# SensorFv.net
KiCad netlist of a schematic drawn in EAGLE
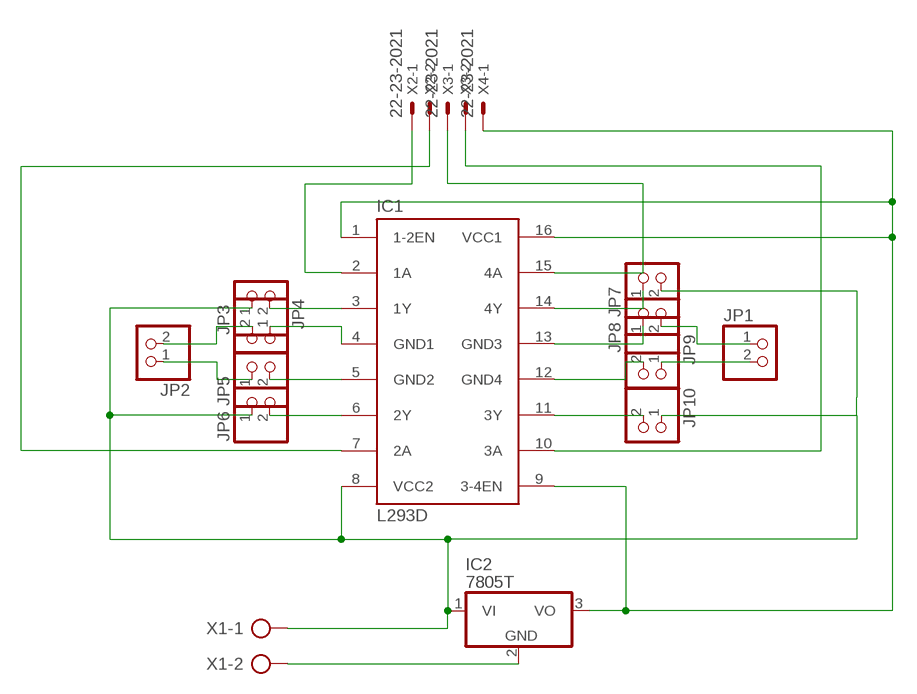
[diagram p0: schematic, sheet 1]

(export (version "E")
  (design (tool "Eeschema 10.0.6"))
  (components
    (comp (ref "IC1")
      (value "L293D")
      (footprint "eagle-import:DIL16")
      (libsource (lib "eagle-import") (part "L293D"))
    )
    (comp (ref "IC2")
      (value "7805T")
      (footprint "eagle-import:TO220H")
      (libsource (lib "eagle-import") (part "78T05"))
    )
    (comp (ref "JP1")
      (value "PINHD-1X2")
      (footprint "eagle-import:1X02")
      (libsource (lib "eagle-import") (part "PINHD-1X2"))
    )
    (comp (ref "JP2")
      (value "PINHD-1X2")
      (footprint "eagle-import:1X02")
      (libsource (lib "eagle-import") (part "PINHD-1X2"))
    )
    (comp (ref "JP3")
      (value "PINHD-1X2")
      (footprint "eagle-import:1X02")
      (libsource (lib "eagle-import") (part "pinhead_325_PINHD-1X2"))
    )
    (comp (ref "JP4")
      (value "PINHD-1X2")
      (footprint "eagle-import:1X02")
      (libsource (lib "eagle-import") (part "pinhead_325_PINHD-1X2"))
    )
    (comp (ref "JP5")
      (value "PINHD-1X2")
      (footprint "eagle-import:1X02")
      (libsource (lib "eagle-import") (part "pinhead_325_PINHD-1X2"))
    )
    (comp (ref "JP6")
      (value "PINHD-1X2")
      (footprint "eagle-import:1X02")
      (libsource (lib "eagle-import") (part "pinhead_325_PINHD-1X2"))
    )
    (comp (ref "JP7")
      (value "PINHD-1X2")
      (footprint "eagle-import:1X02")
      (libsource (lib "eagle-import") (part "pinhead_325_PINHD-1X2"))
    )
    (comp (ref "JP8")
      (value "PINHD-1X2")
      (footprint "eagle-import:1X02")
      (libsource (lib "eagle-import") (part "pinhead_325_PINHD-1X2"))
    )
    (comp (ref "JP9")
      (value "PINHD-1X2")
      (footprint "eagle-import:1X02")
      (libsource (lib "eagle-import") (part "pinhead_325_PINHD-1X2"))
    )
    (comp (ref "JP10")
      (value "PINHD-1X2")
      (footprint "eagle-import:1X02")
      (libsource (lib "eagle-import") (part "pinhead_325_PINHD-1X2"))
    )
    (comp (ref "X1")
      (value "AK500/2-H")
      (footprint "eagle-import:AK500_2-H")
      (libsource (lib "eagle-import") (part "AK500/2-H"))
    )
    (comp (ref "X2")
      (value "22-23-2021")
      (footprint "eagle-import:22-23-2021")
      (fields (field (name "MF") "MOLEX"))
      (libsource (lib "eagle-import") (part "22-23-2021"))
    )
    (comp (ref "X3")
      (value "22-23-2021")
      (footprint "eagle-import:22-23-2021")
      (fields (field (name "MF") "MOLEX"))
      (libsource (lib "eagle-import") (part "22-23-2021"))
    )
    (comp (ref "X4")
      (value "22-23-2021")
      (footprint "eagle-import:22-23-2021")
      (fields (field (name "MF") "MOLEX"))
      (libsource (lib "eagle-import") (part "22-23-2021"))
    )
  )
  (nets
    (net (code "1") (name "Net-(IC1-1-2EN)") (class "Default")
      (node (ref "IC1") (pin "1") (pinfunction "1-2EN_1") (pintype "input"))
      (node (ref "IC1") (pin "16") (pinfunction "VCC1_16") (pintype "power_in"))
      (node (ref "IC1") (pin "9") (pinfunction "3-4EN_9") (pintype "input"))
      (node (ref "IC2") (pin "3") (pinfunction "VO_3") (pintype "passive"))
      (node (ref "X4") (pin "1") (pinfunction "S_1") (pintype "passive"))
    )
    (net (code "2") (name "Net-(IC1-1A)") (class "Default")
      (node (ref "IC1") (pin "2") (pinfunction "1A_2") (pintype "input"))
      (node (ref "X2") (pin "1") (pinfunction "S_1") (pintype "passive"))
    )
    (net (code "3") (name "Net-(IC1-1Y)") (class "Default")
      (node (ref "IC1") (pin "3") (pinfunction "1Y_3") (pintype "output"))
      (node (ref "JP3") (pin "2") (pinfunction "2_2") (pintype "passive"))
    )
    (net (code "4") (name "Net-(IC1-2A)") (class "Default")
      (node (ref "IC1") (pin "7") (pinfunction "2A_7") (pintype "input"))
      (node (ref "X2") (pin "2") (pinfunction "S_2") (pintype "passive"))
    )
    (net (code "5") (name "Net-(IC1-2Y)") (class "Default")
      (node (ref "IC1") (pin "6") (pinfunction "2Y_6") (pintype "output"))
      (node (ref "JP6") (pin "2") (pinfunction "2_2") (pintype "passive"))
    )
    (net (code "6") (name "Net-(IC1-3A)") (class "Default")
      (node (ref "IC1") (pin "10") (pinfunction "3A_10") (pintype "input"))
      (node (ref "X3") (pin "2") (pinfunction "S_2") (pintype "passive"))
    )
    (net (code "7") (name "Net-(IC1-3Y)") (class "Default")
      (node (ref "IC1") (pin "11") (pinfunction "3Y_11") (pintype "output"))
      (node (ref "JP10") (pin "2") (pinfunction "2_2") (pintype "passive"))
    )
    (net (code "8") (name "Net-(IC1-4A)") (class "Default")
      (node (ref "IC1") (pin "15") (pinfunction "4A_15") (pintype "input"))
      (node (ref "X3") (pin "1") (pinfunction "S_1") (pintype "passive"))
    )
    (net (code "9") (name "Net-(IC1-4Y)") (class "Default")
      (node (ref "IC1") (pin "14") (pinfunction "4Y_14") (pintype "output"))
      (node (ref "JP7") (pin "1") (pinfunction "1_1") (pintype "passive"))
    )
    (net (code "10") (name "Net-(IC1-GND1)") (class "Default")
      (node (ref "IC1") (pin "4") (pinfunction "GND1_4") (pintype "power_in"))
      (node (ref "JP4") (pin "1") (pinfunction "1_1") (pintype "passive"))
    )
    (net (code "11") (name "Net-(IC1-GND2)") (class "Default")
      (node (ref "IC1") (pin "5") (pinfunction "GND2_5") (pintype "power_in"))
      (node (ref "JP5") (pin "2") (pinfunction "2_2") (pintype "passive"))
    )
    (net (code "12") (name "Net-(IC1-GND3)") (class "Default")
      (node (ref "IC1") (pin "13") (pinfunction "GND3_13") (pintype "power_in"))
      (node (ref "JP8") (pin "1") (pinfunction "1_1") (pintype "passive"))
    )
    (net (code "13") (name "Net-(IC1-GND4)") (class "Default")
      (node (ref "IC1") (pin "12") (pinfunction "GND4_12") (pintype "power_in"))
      (node (ref "JP9") (pin "2") (pinfunction "2_2") (pintype "passive"))
    )
    (net (code "14") (name "Net-(IC1-VCC2)") (class "Default")
      (node (ref "IC1") (pin "8") (pinfunction "VCC2_8") (pintype "power_in"))
      (node (ref "IC2") (pin "1") (pinfunction "VI_1") (pintype "input"))
      (node (ref "JP10") (pin "1") (pinfunction "1_1") (pintype "passive"))
      (node (ref "JP3") (pin "1") (pinfunction "1_1") (pintype "passive"))
      (node (ref "JP6") (pin "1") (pinfunction "1_1") (pintype "passive"))
      (node (ref "JP7") (pin "2") (pinfunction "2_2") (pintype "passive"))
      (node (ref "X1") (pin "1") (pinfunction "KL_1") (pintype "passive"))
    )
    (net (code "15") (name "Net-(IC2-GND)") (class "Default")
      (node (ref "IC2") (pin "2") (pinfunction "GND_2") (pintype "passive"))
      (node (ref "X1") (pin "2") (pinfunction "KL_2") (pintype "passive"))
    )
    (net (code "16") (name "Net-(JP1-Pad1)") (class "Default")
      (node (ref "JP1") (pin "1") (pinfunction "1_1") (pintype "passive"))
      (node (ref "JP8") (pin "2") (pinfunction "2_2") (pintype "passive"))
    )
    (net (code "17") (name "Net-(JP1-Pad2)") (class "Default")
      (node (ref "JP1") (pin "2") (pinfunction "2_2") (pintype "passive"))
      (node (ref "JP9") (pin "1") (pinfunction "1_1") (pintype "passive"))
    )
    (net (code "18") (name "Net-(JP2-Pad1)") (class "Default")
      (node (ref "JP2") (pin "1") (pinfunction "1_1") (pintype "passive"))
      (node (ref "JP5") (pin "1") (pinfunction "1_1") (pintype "passive"))
    )
    (net (code "19") (name "Net-(JP2-Pad2)") (class "Default")
      (node (ref "JP2") (pin "2") (pinfunction "2_2") (pintype "passive"))
      (node (ref "JP4") (pin "2") (pinfunction "2_2") (pintype "passive"))
    )
  )
)
